# version2.net
KiCad netlist of a schematic drawn in EAGLE
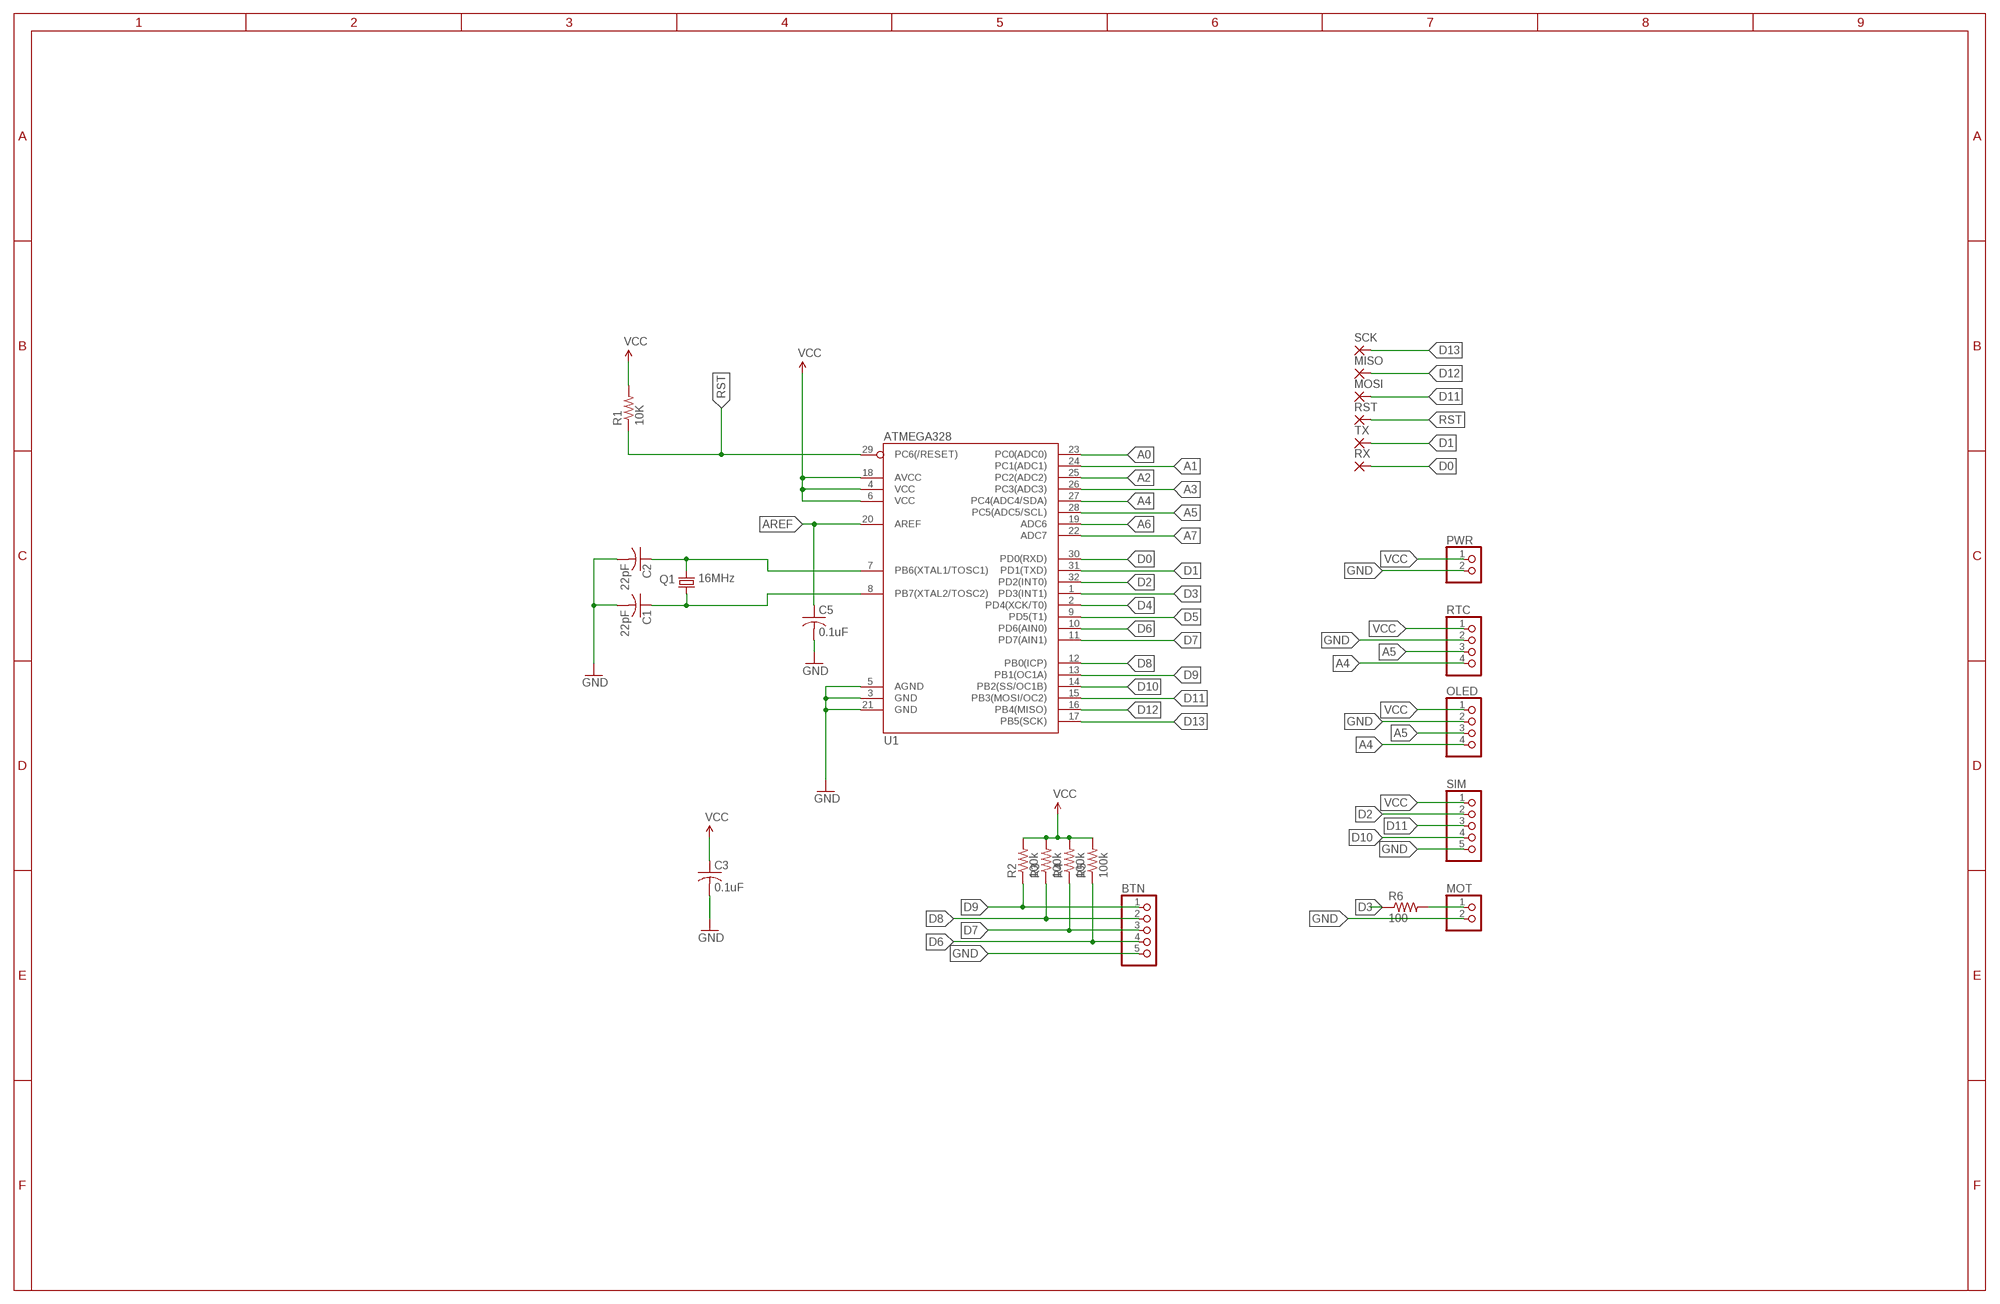
[diagram p0: schematic, sheet 1]

(export (version "E")
  (design (tool "Eeschema 10.0.6"))
  (components
    (comp (ref "BTN")
      (value "PINHD-1X5")
      (footprint "eagle-import:1X05")
      (libsource (lib "eagle-import") (part "PINHD-1X5"))
    )
    (comp (ref "C1")
      (value "22pF")
      (footprint "eagle-import:C1206")
      (libsource (lib "eagle-import") (part "C-USC1206"))
    )
    (comp (ref "C2")
      (value "22pF")
      (footprint "eagle-import:C1206")
      (libsource (lib "eagle-import") (part "C-USC1206"))
    )
    (comp (ref "C3")
      (value "0.1uF")
      (footprint "eagle-import:C0805")
      (libsource (lib "eagle-import") (part "C-USC0805"))
    )
    (comp (ref "C5")
      (value "0.1uF")
      (footprint "eagle-import:C0805")
      (libsource (lib "eagle-import") (part "C-USC0805"))
    )
    (comp (ref "MISO")
      (value "SMD2")
      (footprint "eagle-import:SMD1,27-2,54")
      (libsource (lib "eagle-import") (part "SMD2"))
    )
    (comp (ref "MOSI")
      (value "SMD2")
      (footprint "eagle-import:SMD1,27-2,54")
      (libsource (lib "eagle-import") (part "SMD2"))
    )
    (comp (ref "MOT")
      (value "PINHD-1X2")
      (footprint "eagle-import:1X02")
      (libsource (lib "eagle-import") (part "PINHD-1X2"))
    )
    (comp (ref "OLED")
      (value "PINHD-1X4")
      (footprint "eagle-import:1X04")
      (libsource (lib "eagle-import") (part "PINHD-1X4"))
    )
    (comp (ref "PWR")
      (value "PINHD-1X2")
      (footprint "eagle-import:1X02")
      (libsource (lib "eagle-import") (part "PINHD-1X2"))
    )
    (comp (ref "Q1")
      (value "16MHz")
      (footprint "eagle-import:TC26V")
      (libsource (lib "eagle-import") (part "CRYSTALTC26V"))
    )
    (comp (ref "R1")
      (value "10K")
      (footprint "eagle-import:R1206")
      (libsource (lib "eagle-import") (part "R-US_R1206"))
    )
    (comp (ref "R2")
      (value "100k")
      (footprint "eagle-import:R1206")
      (libsource (lib "eagle-import") (part "R-US_R1206"))
    )
    (comp (ref "R3")
      (value "100k")
      (footprint "eagle-import:R1206")
      (libsource (lib "eagle-import") (part "R-US_R1206"))
    )
    (comp (ref "R4")
      (value "100k")
      (footprint "eagle-import:R1206")
      (libsource (lib "eagle-import") (part "R-US_R1206"))
    )
    (comp (ref "R5")
      (value "100k")
      (footprint "eagle-import:R1206")
      (libsource (lib "eagle-import") (part "R-US_R1206"))
    )
    (comp (ref "R6")
      (value "100")
      (footprint "eagle-import:R1206")
      (libsource (lib "eagle-import") (part "R-US_R1206"))
    )
    (comp (ref "RST")
      (value "SMD2")
      (footprint "eagle-import:SMD1,27-2,54")
      (libsource (lib "eagle-import") (part "SMD2"))
    )
    (comp (ref "RTC")
      (value "PINHD-1X4")
      (footprint "eagle-import:1X04")
      (libsource (lib "eagle-import") (part "PINHD-1X4"))
    )
    (comp (ref "RX")
      (value "SMD2")
      (footprint "eagle-import:SMD1,27-2,54")
      (libsource (lib "eagle-import") (part "SMD2"))
    )
    (comp (ref "SCK")
      (value "SMD2")
      (footprint "eagle-import:SMD1,27-2,54")
      (libsource (lib "eagle-import") (part "SMD2"))
    )
    (comp (ref "SIM")
      (value "PINHD-1X5")
      (footprint "eagle-import:1X05")
      (libsource (lib "eagle-import") (part "PINHD-1X5"))
    )
    (comp (ref "TX")
      (value "SMD2")
      (footprint "eagle-import:SMD1,27-2,54")
      (libsource (lib "eagle-import") (part "SMD2"))
    )
    (comp (ref "U1")
      (value "ATMEGA328")
      (footprint "eagle-import:TQFP32-08")
      (libsource (lib "eagle-import") (part "ATMEGA328"))
    )
  )
  (nets
    (net (code "1") (name "A0") (class "Default")
      (node (ref "U1") (pin "23") (pinfunction "PC0(ADC0)_23") (pintype "bidirectional"))
    )
    (net (code "2") (name "A1") (class "Default")
      (node (ref "U1") (pin "24") (pinfunction "PC1(ADC1)_24") (pintype "bidirectional"))
    )
    (net (code "3") (name "A2") (class "Default")
      (node (ref "U1") (pin "25") (pinfunction "PC2(ADC2)_25") (pintype "bidirectional"))
    )
    (net (code "4") (name "A3") (class "Default")
      (node (ref "U1") (pin "26") (pinfunction "PC3(ADC3)_26") (pintype "bidirectional"))
    )
    (net (code "5") (name "A4") (class "Default")
      (node (ref "OLED") (pin "4") (pinfunction "4_4") (pintype "passive"))
      (node (ref "RTC") (pin "4") (pinfunction "4_4") (pintype "passive"))
      (node (ref "U1") (pin "27") (pinfunction "PC4(ADC4/SDA)_27") (pintype "bidirectional"))
    )
    (net (code "6") (name "A5") (class "Default")
      (node (ref "OLED") (pin "3") (pinfunction "3_3") (pintype "passive"))
      (node (ref "RTC") (pin "3") (pinfunction "3_3") (pintype "passive"))
      (node (ref "U1") (pin "28") (pinfunction "PC5(ADC5/SCL)_28") (pintype "bidirectional"))
    )
    (net (code "7") (name "A6") (class "Default")
      (node (ref "U1") (pin "19") (pinfunction "ADC6_19") (pintype "bidirectional"))
    )
    (net (code "8") (name "A7") (class "Default")
      (node (ref "U1") (pin "22") (pinfunction "ADC7_22") (pintype "bidirectional"))
    )
    (net (code "9") (name "AREF") (class "Default")
      (node (ref "C5") (pin "1") (pinfunction "1_1") (pintype "passive"))
      (node (ref "U1") (pin "20") (pinfunction "AREF_20") (pintype "bidirectional"))
    )
    (net (code "10") (name "D0") (class "Default")
      (node (ref "RX") (pin "1") (pinfunction "P_1") (pintype "passive"))
      (node (ref "U1") (pin "30") (pinfunction "PD0(RXD)_30") (pintype "bidirectional"))
    )
    (net (code "11") (name "D1") (class "Default")
      (node (ref "TX") (pin "1") (pinfunction "P_1") (pintype "passive"))
      (node (ref "U1") (pin "31") (pinfunction "PD1(TXD)_31") (pintype "bidirectional"))
    )
    (net (code "12") (name "D2") (class "Default")
      (node (ref "SIM") (pin "2") (pinfunction "2_2") (pintype "passive"))
      (node (ref "U1") (pin "32") (pinfunction "PD2(INT0)_32") (pintype "bidirectional"))
    )
    (net (code "13") (name "D3") (class "Default")
      (node (ref "R6") (pin "1") (pinfunction "1_1") (pintype "passive"))
      (node (ref "U1") (pin "1") (pinfunction "PD3(INT1)_1") (pintype "bidirectional"))
    )
    (net (code "14") (name "D4") (class "Default")
      (node (ref "U1") (pin "2") (pinfunction "PD4(XCK/T0)_2") (pintype "bidirectional"))
    )
    (net (code "15") (name "D5") (class "Default")
      (node (ref "U1") (pin "9") (pinfunction "PD5(T1)_9") (pintype "bidirectional"))
    )
    (net (code "16") (name "D6") (class "Default")
      (node (ref "BTN") (pin "4") (pinfunction "4_4") (pintype "passive"))
      (node (ref "R5") (pin "1") (pinfunction "1_1") (pintype "passive"))
      (node (ref "U1") (pin "10") (pinfunction "PD6(AIN0)_10") (pintype "bidirectional"))
    )
    (net (code "17") (name "D7") (class "Default")
      (node (ref "BTN") (pin "3") (pinfunction "3_3") (pintype "passive"))
      (node (ref "R4") (pin "1") (pinfunction "1_1") (pintype "passive"))
      (node (ref "U1") (pin "11") (pinfunction "PD7(AIN1)_11") (pintype "bidirectional"))
    )
    (net (code "18") (name "D8") (class "Default")
      (node (ref "BTN") (pin "2") (pinfunction "2_2") (pintype "passive"))
      (node (ref "R3") (pin "1") (pinfunction "1_1") (pintype "passive"))
      (node (ref "U1") (pin "12") (pinfunction "PB0(ICP)_12") (pintype "bidirectional"))
    )
    (net (code "19") (name "D9") (class "Default")
      (node (ref "BTN") (pin "1") (pinfunction "1_1") (pintype "passive"))
      (node (ref "R2") (pin "1") (pinfunction "1_1") (pintype "passive"))
      (node (ref "U1") (pin "13") (pinfunction "PB1(OC1A)_13") (pintype "bidirectional"))
    )
    (net (code "20") (name "D10") (class "Default")
      (node (ref "SIM") (pin "4") (pinfunction "4_4") (pintype "passive"))
      (node (ref "U1") (pin "14") (pinfunction "PB2(SS/OC1B)_14") (pintype "bidirectional"))
    )
    (net (code "21") (name "D11") (class "Default")
      (node (ref "MOSI") (pin "1") (pinfunction "P_1") (pintype "passive"))
      (node (ref "SIM") (pin "3") (pinfunction "3_3") (pintype "passive"))
      (node (ref "U1") (pin "15") (pinfunction "PB3(MOSI/OC2)_15") (pintype "bidirectional"))
    )
    (net (code "22") (name "D12") (class "Default")
      (node (ref "MISO") (pin "1") (pinfunction "P_1") (pintype "passive"))
      (node (ref "U1") (pin "16") (pinfunction "PB4(MISO)_16") (pintype "bidirectional"))
    )
    (net (code "23") (name "D13") (class "Default")
      (node (ref "SCK") (pin "1") (pinfunction "P_1") (pintype "passive"))
      (node (ref "U1") (pin "17") (pinfunction "PB5(SCK)_17") (pintype "bidirectional"))
    )
    (net (code "24") (name "GND") (class "Default")
      (node (ref "BTN") (pin "5") (pinfunction "5_5") (pintype "passive"))
      (node (ref "C1") (pin "2") (pinfunction "2_2") (pintype "passive"))
      (node (ref "C2") (pin "2") (pinfunction "2_2") (pintype "passive"))
      (node (ref "C3") (pin "2") (pinfunction "2_2") (pintype "passive"))
      (node (ref "C5") (pin "2") (pinfunction "2_2") (pintype "passive"))
      (node (ref "MOT") (pin "2") (pinfunction "2_2") (pintype "passive"))
      (node (ref "OLED") (pin "2") (pinfunction "2_2") (pintype "passive"))
      (node (ref "PWR") (pin "2") (pinfunction "2_2") (pintype "passive"))
      (node (ref "RTC") (pin "2") (pinfunction "2_2") (pintype "passive"))
      (node (ref "SIM") (pin "5") (pinfunction "5_5") (pintype "passive"))
      (node (ref "U1") (pin "21") (pinfunction "GND_21") (pintype "bidirectional"))
      (node (ref "U1") (pin "3") (pinfunction "GND_3") (pintype "bidirectional"))
      (node (ref "U1") (pin "5") (pinfunction "AGND_5") (pintype "bidirectional"))
    )
    (net (code "25") (name "Net-(MOT-Pad1)") (class "Default")
      (node (ref "MOT") (pin "1") (pinfunction "1_1") (pintype "passive"))
      (node (ref "R6") (pin "2") (pinfunction "2_2") (pintype "passive"))
    )
    (net (code "26") (name "Net-(U1-PB6(XTAL1{slash}TOSC1))") (class "Default")
      (node (ref "C2") (pin "1") (pinfunction "1_1") (pintype "passive"))
      (node (ref "Q1") (pin "2") (pinfunction "2_2") (pintype "passive"))
      (node (ref "U1") (pin "7") (pinfunction "PB6(XTAL1/TOSC1)_7") (pintype "bidirectional"))
    )
    (net (code "27") (name "Net-(U1-PB7(XTAL2{slash}TOSC2))") (class "Default")
      (node (ref "C1") (pin "1") (pinfunction "1_1") (pintype "passive"))
      (node (ref "Q1") (pin "1") (pinfunction "1_1") (pintype "passive"))
      (node (ref "U1") (pin "8") (pinfunction "PB7(XTAL2/TOSC2)_8") (pintype "bidirectional"))
    )
    (net (code "28") (name "RST") (class "Default")
      (node (ref "R1") (pin "1") (pinfunction "1_1") (pintype "passive"))
      (node (ref "RST") (pin "1") (pinfunction "P_1") (pintype "passive"))
      (node (ref "U1") (pin "29") (pinfunction "PC6(/RESET)_29") (pintype "bidirectional"))
    )
    (net (code "29") (name "VCC") (class "Default")
      (node (ref "C3") (pin "1") (pinfunction "1_1") (pintype "passive"))
      (node (ref "OLED") (pin "1") (pinfunction "1_1") (pintype "passive"))
      (node (ref "PWR") (pin "1") (pinfunction "1_1") (pintype "passive"))
      (node (ref "R1") (pin "2") (pinfunction "2_2") (pintype "passive"))
      (node (ref "R2") (pin "2") (pinfunction "2_2") (pintype "passive"))
      (node (ref "R3") (pin "2") (pinfunction "2_2") (pintype "passive"))
      (node (ref "R4") (pin "2") (pinfunction "2_2") (pintype "passive"))
      (node (ref "R5") (pin "2") (pinfunction "2_2") (pintype "passive"))
      (node (ref "RTC") (pin "1") (pinfunction "1_1") (pintype "passive"))
      (node (ref "SIM") (pin "1") (pinfunction "1_1") (pintype "passive"))
      (node (ref "U1") (pin "18") (pinfunction "AVCC_18") (pintype "bidirectional"))
      (node (ref "U1") (pin "4") (pinfunction "VCC_4") (pintype "bidirectional"))
      (node (ref "U1") (pin "6") (pinfunction "VCC_6") (pintype "bidirectional"))
    )
  )
)
